# box85x85.net
KiCad netlist of a schematic drawn in EAGLE
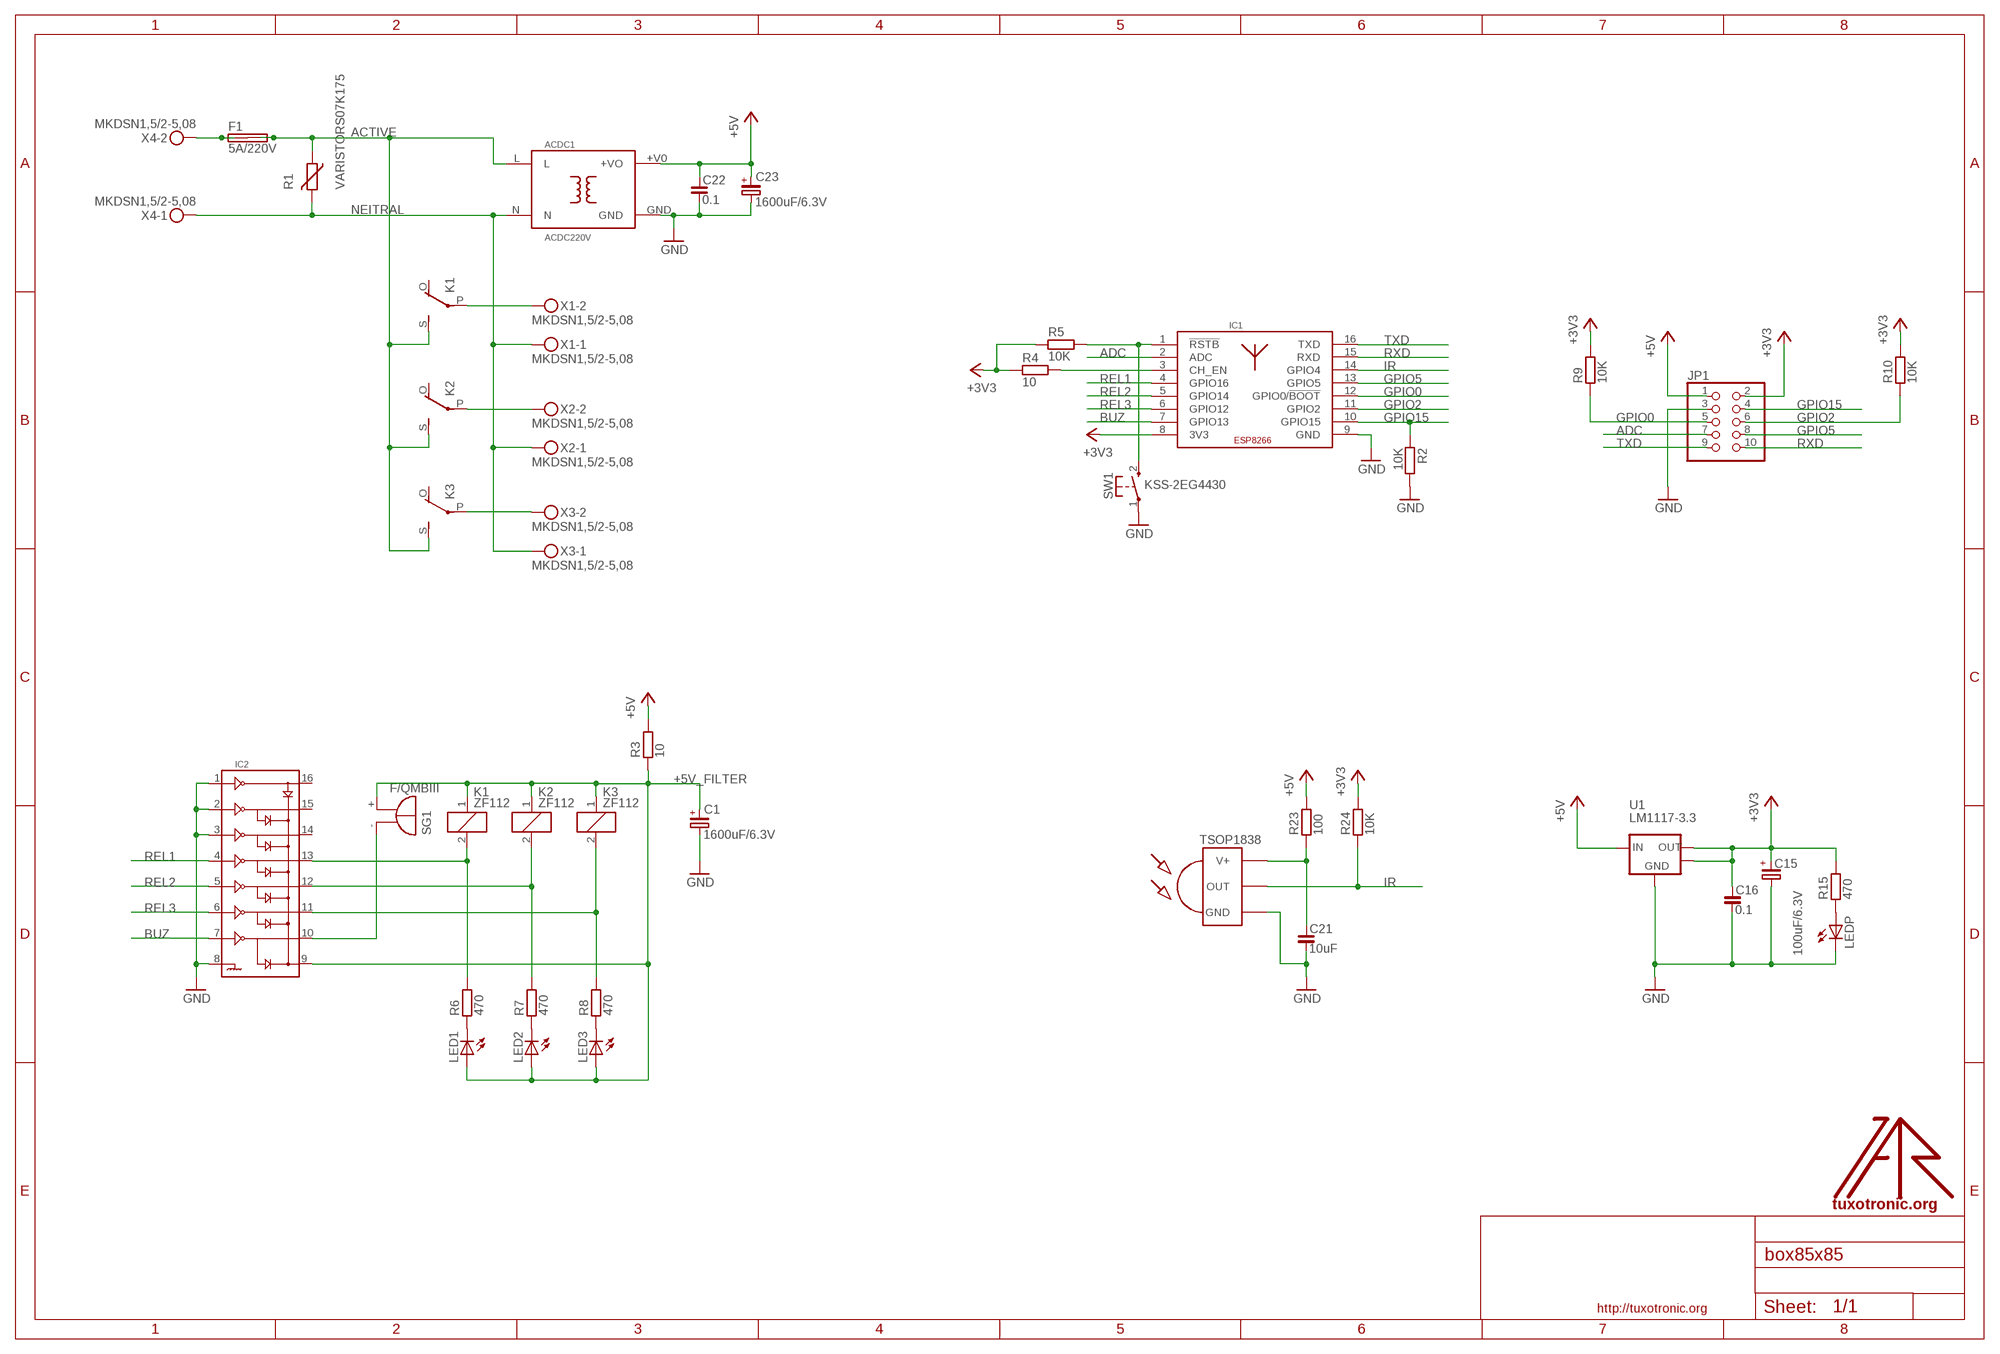
[diagram p0: schematic, sheet 1]

(export (version "E")
  (design (tool "Eeschema 10.0.6"))
  (components
    (comp (ref "ACDC1")
      (value "ACDC220V")
      (footprint "eagle-import:ACDC600MA")
      (libsource (lib "eagle-import") (part "ACDC220V"))
    )
    (comp (ref "C1")
      (value "1600uF/6.3V")
      (footprint "eagle-import:CE-035X080")
      (libsource (lib "eagle-import") (part "CP_E-035X080"))
    )
    (comp (ref "C15")
      (value "100uF/6.3V")
      (footprint "eagle-import:SMC_D")
      (libsource (lib "eagle-import") (part "CP_SMCD"))
    )
    (comp (ref "C16")
      (value "0.1")
      (footprint "eagle-import:C0805")
      (libsource (lib "eagle-import") (part "C_0805"))
    )
    (comp (ref "C21")
      (value "10uF")
      (footprint "eagle-import:C0805")
      (libsource (lib "eagle-import") (part "C_0805"))
    )
    (comp (ref "C22")
      (value "0.1")
      (footprint "eagle-import:C0805")
      (libsource (lib "eagle-import") (part "C_0805"))
    )
    (comp (ref "C23")
      (value "1600uF/6.3V")
      (footprint "eagle-import:CE-035X080")
      (libsource (lib "eagle-import") (part "CP_E-035X080"))
    )
    (comp (ref "F1")
      (value "5A/220V")
      (footprint "eagle-import:SHK20L")
      (libsource (lib "eagle-import") (part "SHK20L"))
    )
    (comp (ref "IC1")
      (value "ESP-12")
      (footprint "eagle-import:ESP12")
      (libsource (lib "eagle-import") (part "ESP-12"))
    )
    (comp (ref "IC2")
      (value "ULN2003D")
      (footprint "eagle-import:SO16")
      (libsource (lib "eagle-import") (part "ULN2003D"))
    )
    (comp (ref "IR1")
      (value "TSOP1838")
      (footprint "eagle-import:TSOP18XX")
      (libsource (lib "eagle-import") (part "TSOP1838"))
    )
    (comp (ref "JP1")
      (value "PINHD-2X5_2.54")
      (footprint "eagle-import:2X05")
      (libsource (lib "eagle-import") (part "PINHD-2X5_2.54"))
    )
    (comp (ref "K1")
      (value "ZF112")
      (footprint "eagle-import:ZF112")
      (libsource (lib "eagle-import") (part "ZF112"))
    )
    (comp (ref "K2")
      (value "ZF112")
      (footprint "eagle-import:ZF112")
      (libsource (lib "eagle-import") (part "ZF112"))
    )
    (comp (ref "K3")
      (value "ZF112")
      (footprint "eagle-import:ZF112")
      (libsource (lib "eagle-import") (part "ZF112"))
    )
    (comp (ref "LED1")
      (value "LED3MM")
      (footprint "eagle-import:LED3MM")
      (libsource (lib "eagle-import") (part "LED3MM"))
    )
    (comp (ref "LED2")
      (value "LED3MM")
      (footprint "eagle-import:LED3MM")
      (libsource (lib "eagle-import") (part "LED3MM"))
    )
    (comp (ref "LED3")
      (value "LED3MM")
      (footprint "eagle-import:LED3MM")
      (libsource (lib "eagle-import") (part "LED3MM"))
    )
    (comp (ref "LEDP")
      (value "LED3MM")
      (footprint "eagle-import:LED3MM")
      (libsource (lib "eagle-import") (part "LED3MM"))
    )
    (comp (ref "R1")
      (value "VARISTORS07K175")
      (footprint "eagle-import:S07K175")
      (libsource (lib "eagle-import") (part "VARISTORS07K175"))
    )
    (comp (ref "R2")
      (value "10K")
      (footprint "eagle-import:R0805")
      (libsource (lib "eagle-import") (part "R_0805"))
    )
    (comp (ref "R3")
      (value "10")
      (footprint "eagle-import:R0805")
      (libsource (lib "eagle-import") (part "R_0805"))
    )
    (comp (ref "R4")
      (value "10")
      (footprint "eagle-import:R0805")
      (libsource (lib "eagle-import") (part "R_0805"))
    )
    (comp (ref "R5")
      (value "10K")
      (footprint "eagle-import:R0805")
      (libsource (lib "eagle-import") (part "R_0805"))
    )
    (comp (ref "R6")
      (value "470")
      (footprint "eagle-import:R0805")
      (libsource (lib "eagle-import") (part "R_0805"))
    )
    (comp (ref "R7")
      (value "470")
      (footprint "eagle-import:R0805")
      (libsource (lib "eagle-import") (part "R_0805"))
    )
    (comp (ref "R8")
      (value "470")
      (footprint "eagle-import:R0805")
      (libsource (lib "eagle-import") (part "R_0805"))
    )
    (comp (ref "R9")
      (value "10K")
      (footprint "eagle-import:R0805")
      (libsource (lib "eagle-import") (part "R_0805"))
    )
    (comp (ref "R10")
      (value "10K")
      (footprint "eagle-import:R0805")
      (libsource (lib "eagle-import") (part "R_0805"))
    )
    (comp (ref "R15")
      (value "470")
      (footprint "eagle-import:R0805")
      (libsource (lib "eagle-import") (part "R_0805"))
    )
    (comp (ref "R23")
      (value "100")
      (footprint "eagle-import:R0805")
      (libsource (lib "eagle-import") (part "R_0805"))
    )
    (comp (ref "R24")
      (value "10K")
      (footprint "eagle-import:R0805")
      (libsource (lib "eagle-import") (part "R_0805"))
    )
    (comp (ref "SG1")
      (value "F/QMBIII")
      (footprint "eagle-import:F_QMBIII")
      (libsource (lib "eagle-import") (part "F/QMBIII"))
    )
    (comp (ref "SW1")
      (value "KSS-2EG4430")
      (footprint "eagle-import:KSS-2EG4430")
      (libsource (lib "eagle-import") (part "KSS-2EG4430"))
    )
    (comp (ref "U$1")
      (value "LOGO")
      (footprint "eagle-import:TT_LOGO")
      (libsource (lib "eagle-import") (part "LOGO"))
    )
    (comp (ref "U1")
      (value "LM1117-3.3")
      (footprint "eagle-import:SOT223")
      (libsource (lib "eagle-import") (part "LM1117-3.3"))
    )
    (comp (ref "X1")
      (value "MKDSN1,5/2-5,08")
      (footprint "eagle-import:MKDSN1,5_2-5,08")
      (libsource (lib "eagle-import") (part "MKDSN1,5/2-5,08"))
    )
    (comp (ref "X2")
      (value "MKDSN1,5/2-5,08")
      (footprint "eagle-import:MKDSN1,5_2-5,08")
      (libsource (lib "eagle-import") (part "MKDSN1,5/2-5,08"))
    )
    (comp (ref "X3")
      (value "MKDSN1,5/2-5,08")
      (footprint "eagle-import:MKDSN1,5_2-5,08")
      (libsource (lib "eagle-import") (part "MKDSN1,5/2-5,08"))
    )
    (comp (ref "X4")
      (value "MKDSN1,5/2-5,08")
      (footprint "eagle-import:MKDSN1,5_2-5,08")
      (libsource (lib "eagle-import") (part "MKDSN1,5/2-5,08"))
    )
  )
  (nets
    (net (code "1") (name "+3V3") (class "Default")
      (node (ref "C15") (pin "+") (pinfunction "+_+") (pintype "passive"))
      (node (ref "C16") (pin "1") (pinfunction "1_1") (pintype "passive"))
      (node (ref "IC1") (pin "8") (pinfunction "3V3_8") (pintype "power_in"))
      (node (ref "JP1") (pin "2") (pinfunction "2_2") (pintype "passive"))
      (node (ref "R10") (pin "2") (pinfunction "2_2") (pintype "passive"))
      (node (ref "R15") (pin "2") (pinfunction "2_2") (pintype "passive"))
      (node (ref "R24") (pin "2") (pinfunction "2_2") (pintype "passive"))
      (node (ref "R4") (pin "1") (pinfunction "1_1") (pintype "passive"))
      (node (ref "R5") (pin "1") (pinfunction "1_1") (pintype "passive"))
      (node (ref "R9") (pin "2") (pinfunction "2_2") (pintype "passive"))
      (node (ref "U1") (pin "2") (pinfunction "OUT_2") (pintype "output"))
      (node (ref "U1") (pin "4") (pinfunction "MASS_4") (pintype "passive"))
    )
    (net (code "2") (name "+5V") (class "Default")
      (node (ref "ACDC1") (pin "+V0") (pinfunction "+VO_+V0") (pintype "power_in"))
      (node (ref "C22") (pin "1") (pinfunction "1_1") (pintype "passive"))
      (node (ref "C23") (pin "+") (pinfunction "+_+") (pintype "passive"))
      (node (ref "JP1") (pin "1") (pinfunction "1_1") (pintype "passive"))
      (node (ref "R23") (pin "2") (pinfunction "2_2") (pintype "passive"))
      (node (ref "R3") (pin "2") (pinfunction "2_2") (pintype "passive"))
      (node (ref "U1") (pin "3") (pinfunction "IN_3") (pintype "power_in"))
    )
    (net (code "3") (name "/+5V_FILTER") (class "Default")
      (node (ref "C1") (pin "+") (pinfunction "+_+") (pintype "passive"))
      (node (ref "IC2") (pin "9") (pinfunction "9_9") (pintype "power_in"))
      (node (ref "K1") (pin "1") (pinfunction "1_1") (pintype "passive"))
      (node (ref "K2") (pin "1") (pinfunction "1_1") (pintype "passive"))
      (node (ref "K3") (pin "1") (pinfunction "1_1") (pintype "passive"))
      (node (ref "LED1") (pin "A") (pinfunction "A_A") (pintype "passive"))
      (node (ref "LED2") (pin "A") (pinfunction "A_A") (pintype "passive"))
      (node (ref "LED3") (pin "A") (pinfunction "A_A") (pintype "passive"))
      (node (ref "R3") (pin "1") (pinfunction "1_1") (pintype "passive"))
      (node (ref "SG1") (pin "+") (pinfunction "-_+") (pintype "passive"))
    )
    (net (code "4") (name "/ACTIVE") (class "Default")
      (node (ref "ACDC1") (pin "L") (pinfunction "L_L") (pintype "power_in"))
      (node (ref "F1") (pin "2A") (pinfunction "2A_2A") (pintype "passive"))
      (node (ref "F1") (pin "2B") (pinfunction "2B_2B") (pintype "passive"))
      (node (ref "K1") (pin "S") (pinfunction "S_S") (pintype "passive"))
      (node (ref "K2") (pin "S") (pinfunction "S_S") (pintype "passive"))
      (node (ref "K3") (pin "S") (pinfunction "S_S") (pintype "passive"))
      (node (ref "R1") (pin "1") (pinfunction "1_1") (pintype "passive"))
    )
    (net (code "5") (name "/ADC") (class "Default")
      (node (ref "IC1") (pin "2") (pinfunction "ADC_2") (pintype "input"))
      (node (ref "JP1") (pin "7") (pinfunction "7_7") (pintype "passive"))
    )
    (net (code "6") (name "/BUZ") (class "Default")
      (node (ref "IC1") (pin "7") (pinfunction "GPIO13_7") (pintype "bidirectional"))
      (node (ref "IC2") (pin "7") (pinfunction "7_7") (pintype "input"))
    )
    (net (code "7") (name "/GPIO0") (class "Default")
      (node (ref "IC1") (pin "12") (pinfunction "GPIO0/~{BOOT}_12") (pintype "bidirectional"))
      (node (ref "JP1") (pin "5") (pinfunction "5_5") (pintype "passive"))
      (node (ref "R9") (pin "1") (pinfunction "1_1") (pintype "passive"))
    )
    (net (code "8") (name "/GPIO2") (class "Default")
      (node (ref "IC1") (pin "11") (pinfunction "GPIO2_11") (pintype "bidirectional"))
      (node (ref "JP1") (pin "6") (pinfunction "6_6") (pintype "passive"))
      (node (ref "R10") (pin "1") (pinfunction "1_1") (pintype "passive"))
    )
    (net (code "9") (name "/GPIO5") (class "Default")
      (node (ref "IC1") (pin "13") (pinfunction "GPIO5_13") (pintype "bidirectional"))
      (node (ref "JP1") (pin "8") (pinfunction "8_8") (pintype "passive"))
    )
    (net (code "10") (name "/GPIO15") (class "Default")
      (node (ref "IC1") (pin "10") (pinfunction "GPIO15_10") (pintype "bidirectional"))
      (node (ref "JP1") (pin "4") (pinfunction "4_4") (pintype "passive"))
      (node (ref "R2") (pin "1") (pinfunction "1_1") (pintype "passive"))
    )
    (net (code "11") (name "/IR") (class "Default")
      (node (ref "IC1") (pin "14") (pinfunction "GPIO4_14") (pintype "bidirectional"))
      (node (ref "IR1") (pin "OUT") (pinfunction "OUT_OUT") (pintype "bidirectional"))
      (node (ref "R24") (pin "1") (pinfunction "1_1") (pintype "passive"))
    )
    (net (code "12") (name "/NEITRAL") (class "Default")
      (node (ref "ACDC1") (pin "N") (pinfunction "N_N") (pintype "power_in"))
      (node (ref "R1") (pin "2") (pinfunction "2_2") (pintype "passive"))
      (node (ref "X1") (pin "1") (pinfunction "KL_1") (pintype "passive"))
      (node (ref "X2") (pin "1") (pinfunction "KL_1") (pintype "passive"))
      (node (ref "X3") (pin "1") (pinfunction "KL_1") (pintype "passive"))
      (node (ref "X4") (pin "1") (pinfunction "KL_1") (pintype "passive"))
    )
    (net (code "13") (name "/REL1") (class "Default")
      (node (ref "IC1") (pin "4") (pinfunction "GPIO16_4") (pintype "bidirectional"))
      (node (ref "IC2") (pin "4") (pinfunction "4_4") (pintype "input"))
    )
    (net (code "14") (name "/REL2") (class "Default")
      (node (ref "IC1") (pin "5") (pinfunction "GPIO14_5") (pintype "bidirectional"))
      (node (ref "IC2") (pin "5") (pinfunction "5_5") (pintype "input"))
    )
    (net (code "15") (name "/REL3") (class "Default")
      (node (ref "IC1") (pin "6") (pinfunction "GPIO12_6") (pintype "bidirectional"))
      (node (ref "IC2") (pin "6") (pinfunction "6_6") (pintype "input"))
    )
    (net (code "16") (name "/RXD") (class "Default")
      (node (ref "IC1") (pin "15") (pinfunction "RXD_15") (pintype "input"))
      (node (ref "JP1") (pin "10") (pinfunction "10_10") (pintype "passive"))
    )
    (net (code "17") (name "/TXD") (class "Default")
      (node (ref "IC1") (pin "16") (pinfunction "TXD_16") (pintype "output"))
      (node (ref "JP1") (pin "9") (pinfunction "9_9") (pintype "passive"))
    )
    (net (code "18") (name "GND") (class "Default")
      (node (ref "ACDC1") (pin "GND") (pinfunction "GND_GND") (pintype "power_in"))
      (node (ref "C1") (pin "-") (pinfunction "-_-") (pintype "passive"))
      (node (ref "C15") (pin "-") (pinfunction "-_-") (pintype "passive"))
      (node (ref "C16") (pin "2") (pinfunction "2_2") (pintype "passive"))
      (node (ref "C21") (pin "2") (pinfunction "2_2") (pintype "passive"))
      (node (ref "C22") (pin "2") (pinfunction "2_2") (pintype "passive"))
      (node (ref "C23") (pin "-") (pinfunction "-_-") (pintype "passive"))
      (node (ref "IC1") (pin "9") (pinfunction "GND_9") (pintype "power_in"))
      (node (ref "IC2") (pin "1") (pinfunction "1_1") (pintype "input"))
      (node (ref "IC2") (pin "2") (pinfunction "2_2") (pintype "input"))
      (node (ref "IC2") (pin "3") (pinfunction "3_3") (pintype "input"))
      (node (ref "IC2") (pin "8") (pinfunction "8_8") (pintype "power_in"))
      (node (ref "IR1") (pin "GND") (pinfunction "GND_GND") (pintype "bidirectional"))
      (node (ref "JP1") (pin "3") (pinfunction "3_3") (pintype "passive"))
      (node (ref "LEDP") (pin "K") (pinfunction "C_K") (pintype "passive"))
      (node (ref "R2") (pin "2") (pinfunction "2_2") (pintype "passive"))
      (node (ref "SW1") (pin "1") (pinfunction "P_1") (pintype "passive"))
      (node (ref "U1") (pin "1") (pinfunction "GND_1") (pintype "power_in"))
    )
    (net (code "19") (name "Net-(IC1-CH_EN)") (class "Default")
      (node (ref "IC1") (pin "3") (pinfunction "CH_EN_3") (pintype "input"))
      (node (ref "R4") (pin "2") (pinfunction "2_2") (pintype "passive"))
    )
    (net (code "20") (name "Net-(IC1-~{RSTB})") (class "Default")
      (node (ref "IC1") (pin "1") (pinfunction "~{RSTB}_1") (pintype "input"))
      (node (ref "R5") (pin "2") (pinfunction "2_2") (pintype "passive"))
      (node (ref "SW1") (pin "2") (pinfunction "S_2") (pintype "passive"))
    )
    (net (code "21") (name "Net-(IC2-Pad11)") (class "Default")
      (node (ref "IC2") (pin "11") (pinfunction "11_11") (pintype "open_collector"))
      (node (ref "K3") (pin "2") (pinfunction "2_2") (pintype "passive"))
      (node (ref "R8") (pin "2") (pinfunction "2_2") (pintype "passive"))
    )
    (net (code "22") (name "Net-(IC2-Pad12)") (class "Default")
      (node (ref "IC2") (pin "12") (pinfunction "12_12") (pintype "open_collector"))
      (node (ref "K2") (pin "2") (pinfunction "2_2") (pintype "passive"))
      (node (ref "R7") (pin "2") (pinfunction "2_2") (pintype "passive"))
    )
    (net (code "23") (name "Net-(IC2-Pad13)") (class "Default")
      (node (ref "IC2") (pin "13") (pinfunction "13_13") (pintype "open_collector"))
      (node (ref "K1") (pin "2") (pinfunction "2_2") (pintype "passive"))
      (node (ref "R6") (pin "2") (pinfunction "2_2") (pintype "passive"))
    )
    (net (code "24") (name "Net-(IR1-V+)") (class "Default")
      (node (ref "C21") (pin "1") (pinfunction "1_1") (pintype "passive"))
      (node (ref "IR1") (pin "VCC") (pinfunction "V+_VCC") (pintype "bidirectional"))
      (node (ref "R23") (pin "1") (pinfunction "1_1") (pintype "passive"))
    )
    (net (code "25") (name "Net-(LED1-C)") (class "Default")
      (node (ref "LED1") (pin "K") (pinfunction "C_K") (pintype "passive"))
      (node (ref "R6") (pin "1") (pinfunction "1_1") (pintype "passive"))
    )
    (net (code "26") (name "Net-(LED2-C)") (class "Default")
      (node (ref "LED2") (pin "K") (pinfunction "C_K") (pintype "passive"))
      (node (ref "R7") (pin "1") (pinfunction "1_1") (pintype "passive"))
    )
    (net (code "27") (name "Net-(LED3-C)") (class "Default")
      (node (ref "LED3") (pin "K") (pinfunction "C_K") (pintype "passive"))
      (node (ref "R8") (pin "1") (pinfunction "1_1") (pintype "passive"))
    )
    (net (code "28") (name "Net-(LEDP-PadA)") (class "Default")
      (node (ref "LEDP") (pin "A") (pinfunction "A_A") (pintype "passive"))
      (node (ref "R15") (pin "1") (pinfunction "1_1") (pintype "passive"))
    )
    (net (code "29") (name "Net-(SG1-+)") (class "Default")
      (node (ref "IC2") (pin "10") (pinfunction "10_10") (pintype "open_collector"))
      (node (ref "SG1") (pin "-") (pinfunction "+_-") (pintype "passive"))
    )
    (net (code "30") (name "Net-(X1B-KL)") (class "Default")
      (node (ref "K1") (pin "P") (pinfunction "P_P") (pintype "passive"))
      (node (ref "X1") (pin "2") (pinfunction "KL_2") (pintype "passive"))
    )
    (net (code "31") (name "Net-(X2B-KL)") (class "Default")
      (node (ref "K2") (pin "P") (pinfunction "P_P") (pintype "passive"))
      (node (ref "X2") (pin "2") (pinfunction "KL_2") (pintype "passive"))
    )
    (net (code "32") (name "Net-(X3B-KL)") (class "Default")
      (node (ref "K3") (pin "P") (pinfunction "P_P") (pintype "passive"))
      (node (ref "X3") (pin "2") (pinfunction "KL_2") (pintype "passive"))
    )
    (net (code "33") (name "Net-(X4B-KL)") (class "Default")
      (node (ref "F1") (pin "1A") (pinfunction "1A_1A") (pintype "passive"))
      (node (ref "F1") (pin "1B") (pinfunction "1B_1B") (pintype "passive"))
      (node (ref "X4") (pin "2") (pinfunction "KL_2") (pintype "passive"))
    )
    (net (code "34") (name "unconnected-(IC2-Pad14)") (class "Default")
      (node (ref "IC2") (pin "14") (pinfunction "14_14") (pintype "open_collector"))
    )
    (net (code "35") (name "unconnected-(IC2-Pad15)") (class "Default")
      (node (ref "IC2") (pin "15") (pinfunction "15_15") (pintype "open_collector"))
    )
    (net (code "36") (name "unconnected-(IC2-Pad16)") (class "Default")
      (node (ref "IC2") (pin "16") (pinfunction "16_16") (pintype "open_collector"))
    )
    (net (code "37") (name "unconnected-(K1-PadO)") (class "Default")
      (node (ref "K1") (pin "O") (pinfunction "O_O") (pintype "passive"))
    )
    (net (code "38") (name "unconnected-(K2-PadO)") (class "Default")
      (node (ref "K2") (pin "O") (pinfunction "O_O") (pintype "passive"))
    )
    (net (code "39") (name "unconnected-(K3-PadO)") (class "Default")
      (node (ref "K3") (pin "O") (pinfunction "O_O") (pintype "passive"))
    )
  )
)
